# ws2182b_LED_string.net
KiCad netlist of a schematic drawn in Altium Designer
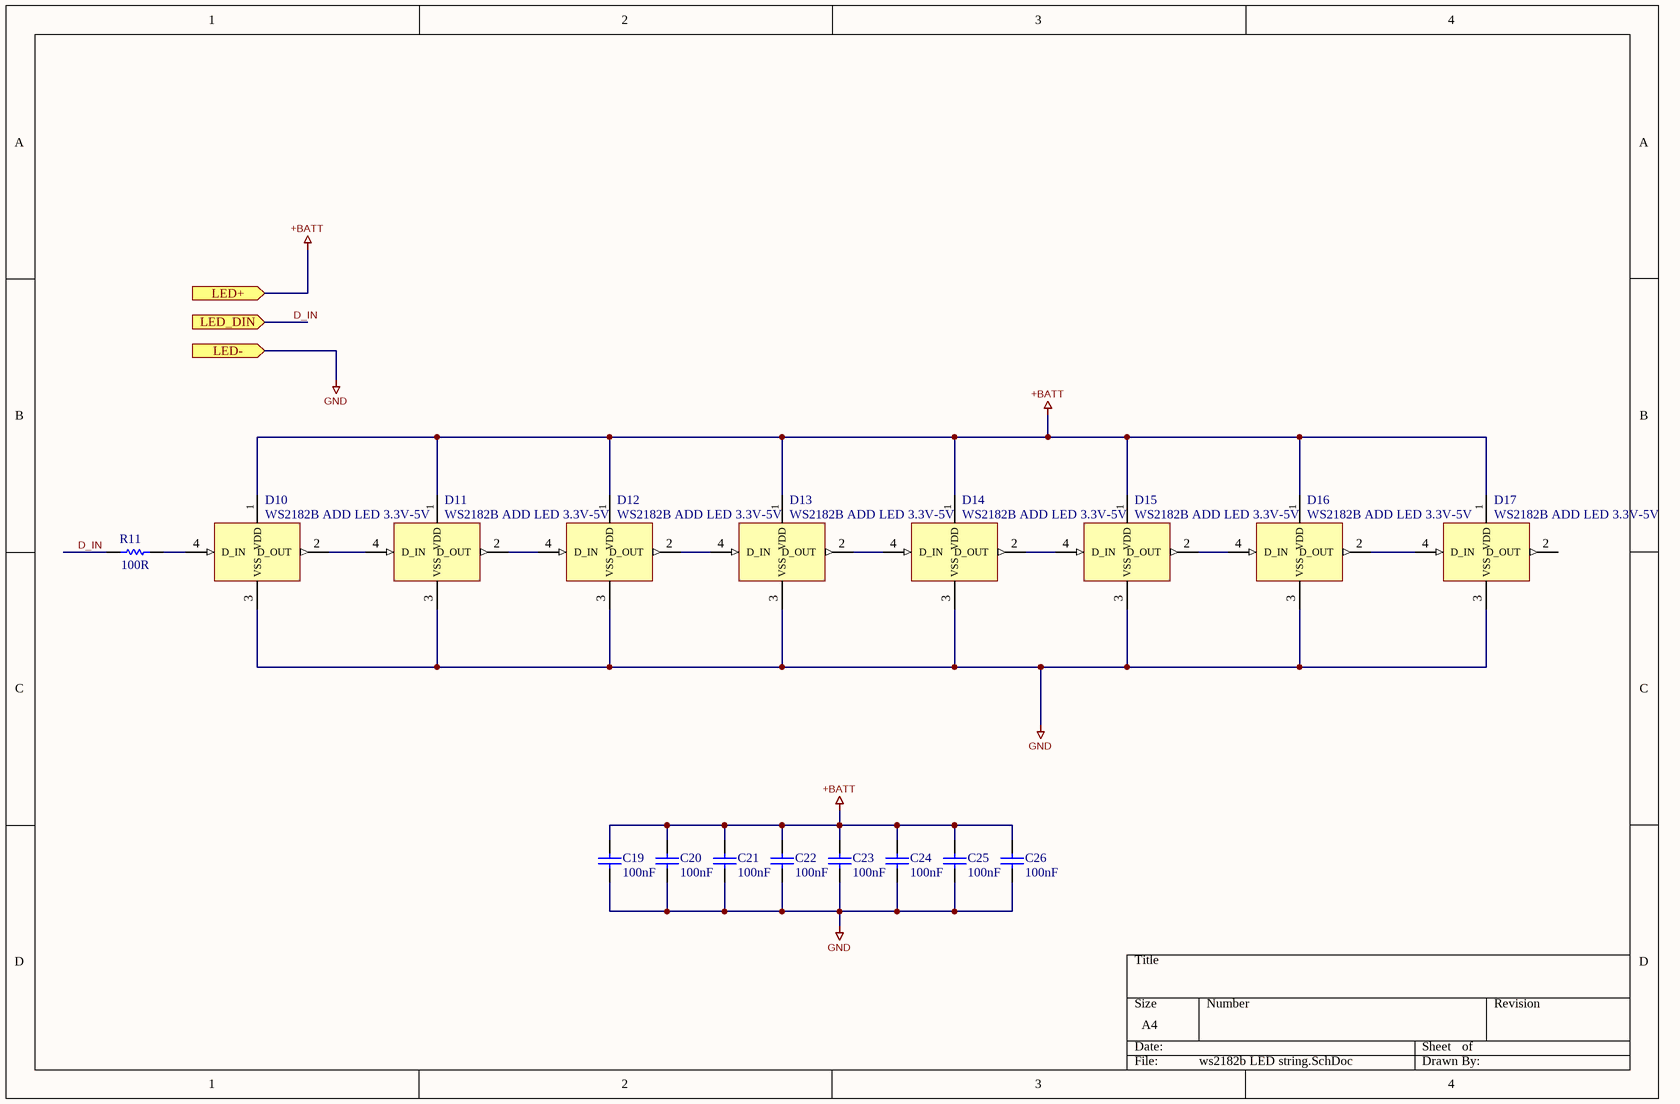
[diagram p0: ws2182b LED string.SchDoc]

(export (version "E")
  (design (tool "Eeschema 10.0.6"))
  (components
    (comp (ref "C19")
      (value "100nF")
      (footprint "CAPC1608X90X20LL10")
      (description "Chip Capacitor, 0.1 uF, +/- 10%, 50 V, -55 to 125 degC, 0603 (1608 Metric), RoHS, Tape and Reel")
      (fields (field (name "VOLTAGE") "50V") (field (name "TOLERANCE") "10%"))
      (libsource (lib "Altium Content Vault") (part "CAP-NP-2"))
    )
    (comp (ref "C20")
      (value "100nF")
      (footprint "CAPC1608X90X20LL10")
      (description "Chip Capacitor, 0.1 uF, +/- 10%, 50 V, -55 to 125 degC, 0603 (1608 Metric), RoHS, Tape and Reel")
      (fields (field (name "VOLTAGE") "50V") (field (name "TOLERANCE") "10%"))
      (libsource (lib "Altium Content Vault") (part "CAP-NP-2"))
    )
    (comp (ref "C21")
      (value "100nF")
      (footprint "CAPC1608X90X20LL10")
      (description "Chip Capacitor, 0.1 uF, +/- 10%, 50 V, -55 to 125 degC, 0603 (1608 Metric), RoHS, Tape and Reel")
      (fields (field (name "VOLTAGE") "50V") (field (name "TOLERANCE") "10%"))
      (libsource (lib "Altium Content Vault") (part "CAP-NP-2"))
    )
    (comp (ref "C22")
      (value "100nF")
      (footprint "CAPC1608X90X20LL10")
      (description "Chip Capacitor, 0.1 uF, +/- 10%, 50 V, -55 to 125 degC, 0603 (1608 Metric), RoHS, Tape and Reel")
      (fields (field (name "VOLTAGE") "50V") (field (name "TOLERANCE") "10%"))
      (libsource (lib "Altium Content Vault") (part "CAP-NP-2"))
    )
    (comp (ref "C23")
      (value "100nF")
      (footprint "CAPC1608X90X20LL10")
      (description "Chip Capacitor, 0.1 uF, +/- 10%, 50 V, -55 to 125 degC, 0603 (1608 Metric), RoHS, Tape and Reel")
      (fields (field (name "VOLTAGE") "50V") (field (name "TOLERANCE") "10%"))
      (libsource (lib "Altium Content Vault") (part "CAP-NP-2"))
    )
    (comp (ref "C24")
      (value "100nF")
      (footprint "CAPC1608X90X20LL10")
      (description "Chip Capacitor, 0.1 uF, +/- 10%, 50 V, -55 to 125 degC, 0603 (1608 Metric), RoHS, Tape and Reel")
      (fields (field (name "VOLTAGE") "50V") (field (name "TOLERANCE") "10%"))
      (libsource (lib "Altium Content Vault") (part "CAP-NP-2"))
    )
    (comp (ref "C25")
      (value "100nF")
      (footprint "CAPC1608X90X20LL10")
      (description "Chip Capacitor, 0.1 uF, +/- 10%, 50 V, -55 to 125 degC, 0603 (1608 Metric), RoHS, Tape and Reel")
      (fields (field (name "VOLTAGE") "50V") (field (name "TOLERANCE") "10%"))
      (libsource (lib "Altium Content Vault") (part "CAP-NP-2"))
    )
    (comp (ref "C26")
      (value "100nF")
      (footprint "CAPC1608X90X20LL10")
      (description "Chip Capacitor, 0.1 uF, +/- 10%, 50 V, -55 to 125 degC, 0603 (1608 Metric), RoHS, Tape and Reel")
      (fields (field (name "VOLTAGE") "50V") (field (name "TOLERANCE") "10%"))
      (libsource (lib "Altium Content Vault") (part "CAP-NP-2"))
    )
    (comp (ref "D10")
      (value "WS2182B ADD LED 3.3V-5V")
      (footprint "WS2182B")
      (libsource (lib "PlumPot_Library") (part "WS2182B"))
    )
    (comp (ref "D11")
      (value "WS2182B ADD LED 3.3V-5V")
      (footprint "WS2182B")
      (libsource (lib "PlumPot_Library") (part "WS2182B"))
    )
    (comp (ref "D12")
      (value "WS2182B ADD LED 3.3V-5V")
      (footprint "WS2182B")
      (libsource (lib "PlumPot_Library") (part "WS2182B"))
    )
    (comp (ref "D13")
      (value "WS2182B ADD LED 3.3V-5V")
      (footprint "WS2182B")
      (libsource (lib "PlumPot_Library") (part "WS2182B"))
    )
    (comp (ref "D14")
      (value "WS2182B ADD LED 3.3V-5V")
      (footprint "WS2182B")
      (libsource (lib "PlumPot_Library") (part "WS2182B"))
    )
    (comp (ref "D15")
      (value "WS2182B ADD LED 3.3V-5V")
      (footprint "WS2182B")
      (libsource (lib "PlumPot_Library") (part "WS2182B"))
    )
    (comp (ref "D16")
      (value "WS2182B ADD LED 3.3V-5V")
      (footprint "WS2182B")
      (libsource (lib "PlumPot_Library") (part "WS2182B"))
    )
    (comp (ref "D17")
      (value "WS2182B ADD LED 3.3V-5V")
      (footprint "WS2182B")
      (libsource (lib "PlumPot_Library") (part "WS2182B"))
    )
    (comp (ref "R11")
      (value "100R")
      (footprint "RESC1608X55X25LL10T15")
      (libsource (lib "Altium Content Vault") (part "RES-2"))
    )
  )
  (nets
    (net (code "1") (name "+BATT") (class "Default")
      (node (ref "C19") (pin "2") (pinfunction "2_2") (pintype "passive"))
      (node (ref "C20") (pin "2") (pinfunction "2_2") (pintype "passive"))
      (node (ref "C21") (pin "2") (pinfunction "2_2") (pintype "passive"))
      (node (ref "C22") (pin "2") (pinfunction "2_2") (pintype "passive"))
      (node (ref "C23") (pin "2") (pinfunction "2_2") (pintype "passive"))
      (node (ref "C24") (pin "2") (pinfunction "2_2") (pintype "passive"))
      (node (ref "C25") (pin "2") (pinfunction "2_2") (pintype "passive"))
      (node (ref "C26") (pin "2") (pinfunction "2_2") (pintype "passive"))
      (node (ref "D10") (pin "1") (pinfunction "VDD_1") (pintype "passive"))
      (node (ref "D11") (pin "1") (pinfunction "VDD_1") (pintype "passive"))
      (node (ref "D12") (pin "1") (pinfunction "VDD_1") (pintype "passive"))
      (node (ref "D13") (pin "1") (pinfunction "VDD_1") (pintype "passive"))
      (node (ref "D14") (pin "1") (pinfunction "VDD_1") (pintype "passive"))
      (node (ref "D15") (pin "1") (pinfunction "VDD_1") (pintype "passive"))
      (node (ref "D16") (pin "1") (pinfunction "VDD_1") (pintype "passive"))
      (node (ref "D17") (pin "1") (pinfunction "VDD_1") (pintype "passive"))
    )
    (net (code "2") (name "/D_IN") (class "Default")
      (node (ref "R11") (pin "1") (pinfunction "1_1") (pintype "passive"))
    )
    (net (code "3") (name "GND") (class "Default")
      (node (ref "C19") (pin "1") (pinfunction "1_1") (pintype "passive"))
      (node (ref "C20") (pin "1") (pinfunction "1_1") (pintype "passive"))
      (node (ref "C21") (pin "1") (pinfunction "1_1") (pintype "passive"))
      (node (ref "C22") (pin "1") (pinfunction "1_1") (pintype "passive"))
      (node (ref "C23") (pin "1") (pinfunction "1_1") (pintype "passive"))
      (node (ref "C24") (pin "1") (pinfunction "1_1") (pintype "passive"))
      (node (ref "C25") (pin "1") (pinfunction "1_1") (pintype "passive"))
      (node (ref "C26") (pin "1") (pinfunction "1_1") (pintype "passive"))
      (node (ref "D10") (pin "3") (pinfunction "VSS_3") (pintype "passive"))
      (node (ref "D11") (pin "3") (pinfunction "VSS_3") (pintype "passive"))
      (node (ref "D12") (pin "3") (pinfunction "VSS_3") (pintype "passive"))
      (node (ref "D13") (pin "3") (pinfunction "VSS_3") (pintype "passive"))
      (node (ref "D14") (pin "3") (pinfunction "VSS_3") (pintype "passive"))
      (node (ref "D15") (pin "3") (pinfunction "VSS_3") (pintype "passive"))
      (node (ref "D16") (pin "3") (pinfunction "VSS_3") (pintype "passive"))
      (node (ref "D17") (pin "3") (pinfunction "VSS_3") (pintype "passive"))
    )
    (net (code "4") (name "Net-(D10-D_IN)") (class "Default")
      (node (ref "D10") (pin "4") (pinfunction "D_IN_4") (pintype "input"))
      (node (ref "R11") (pin "2") (pinfunction "2_2") (pintype "passive"))
    )
    (net (code "5") (name "Net-(D10-D_OUT)") (class "Default")
      (node (ref "D10") (pin "2") (pinfunction "D_OUT_2") (pintype "output"))
      (node (ref "D11") (pin "4") (pinfunction "D_IN_4") (pintype "input"))
    )
    (net (code "6") (name "Net-(D11-D_OUT)") (class "Default")
      (node (ref "D11") (pin "2") (pinfunction "D_OUT_2") (pintype "output"))
      (node (ref "D12") (pin "4") (pinfunction "D_IN_4") (pintype "input"))
    )
    (net (code "7") (name "Net-(D12-D_OUT)") (class "Default")
      (node (ref "D12") (pin "2") (pinfunction "D_OUT_2") (pintype "output"))
      (node (ref "D13") (pin "4") (pinfunction "D_IN_4") (pintype "input"))
    )
    (net (code "8") (name "Net-(D13-D_OUT)") (class "Default")
      (node (ref "D13") (pin "2") (pinfunction "D_OUT_2") (pintype "output"))
      (node (ref "D14") (pin "4") (pinfunction "D_IN_4") (pintype "input"))
    )
    (net (code "9") (name "Net-(D14-D_OUT)") (class "Default")
      (node (ref "D14") (pin "2") (pinfunction "D_OUT_2") (pintype "output"))
      (node (ref "D15") (pin "4") (pinfunction "D_IN_4") (pintype "input"))
    )
    (net (code "10") (name "Net-(D15-D_OUT)") (class "Default")
      (node (ref "D15") (pin "2") (pinfunction "D_OUT_2") (pintype "output"))
      (node (ref "D16") (pin "4") (pinfunction "D_IN_4") (pintype "input"))
    )
    (net (code "11") (name "Net-(D16-D_OUT)") (class "Default")
      (node (ref "D16") (pin "2") (pinfunction "D_OUT_2") (pintype "output"))
      (node (ref "D17") (pin "4") (pinfunction "D_IN_4") (pintype "input"))
    )
    (net (code "12") (name "unconnected-(D17-D_OUT-Pad2)") (class "Default")
      (node (ref "D17") (pin "2") (pinfunction "D_OUT_2") (pintype "output"))
    )
  )
)
